# USB_Micro_Power_to_lab_board_2015-12-31.net
KiCad netlist of a schematic drawn in EAGLE
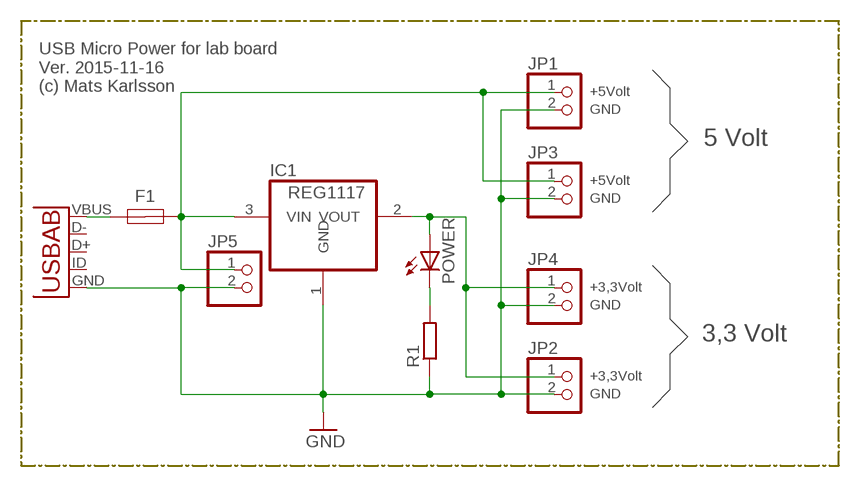
[diagram p0: schematic, sheet 1]

(export (version "E")
  (design (tool "Eeschema 10.0.6"))
  (components
    (comp (ref "F1")
      (value "LITTELFUSE_1812_500MA")
      (footprint "eagle-import:R1812")
      (fields (field (name "MPN") "1812L050PR"))
      (libsource (lib "eagle-import") (part "LITTELFUSE_1812_500MA"))
    )
    (comp (ref "IC1")
      (value "REG1117")
      (footprint "eagle-import:SOT223")
      (libsource (lib "eagle-import") (part "REG1117"))
    )
    (comp (ref "JP1")
      (value "PINHD-1X2")
      (footprint "eagle-import:1X02")
      (libsource (lib "eagle-import") (part "PINHD-1X2"))
    )
    (comp (ref "JP2")
      (value "PINHD-1X2")
      (footprint "eagle-import:1X02")
      (libsource (lib "eagle-import") (part "PINHD-1X2"))
    )
    (comp (ref "JP3")
      (value "PINHD-1X2")
      (footprint "eagle-import:1X02")
      (libsource (lib "eagle-import") (part "PINHD-1X2"))
    )
    (comp (ref "JP4")
      (value "PINHD-1X2")
      (footprint "eagle-import:1X02")
      (libsource (lib "eagle-import") (part "PINHD-1X2"))
    )
    (comp (ref "JP5")
      (value "PINHD-1X2")
      (footprint "eagle-import:1X02")
      (libsource (lib "eagle-import") (part "PINHD-1X2"))
    )
    (comp (ref "POWER")
      (value "LED3MM")
      (footprint "eagle-import:LED3MM")
      (libsource (lib "eagle-import") (part "LED3MM"))
    )
    (comp (ref "R1")
      (value "R-EU_0204/5")
      (footprint "eagle-import:0204_5")
      (libsource (lib "eagle-import") (part "R-EU_0204/5"))
    )
    (comp (ref "U1")
      (value "USB-ABUSB-AB-MICRO-SMD")
      (footprint "eagle-import:USB-AB-MICRO-SMD_VO2")
      (libsource (lib "eagle-import") (part "USB-ABUSB-AB-MICRO-SMD"))
    )
  )
  (nets
    (net (code "1") (name "GND") (class "Default")
      (node (ref "IC1") (pin "1") (pinfunction "GND_1") (pintype "power_in"))
      (node (ref "JP1") (pin "2") (pinfunction "2_2") (pintype "passive"))
      (node (ref "JP2") (pin "2") (pinfunction "2_2") (pintype "passive"))
      (node (ref "JP3") (pin "2") (pinfunction "2_2") (pintype "passive"))
      (node (ref "JP4") (pin "2") (pinfunction "2_2") (pintype "passive"))
      (node (ref "JP5") (pin "2") (pinfunction "2_2") (pintype "passive"))
      (node (ref "R1") (pin "1") (pinfunction "1_1") (pintype "passive"))
      (node (ref "U1") (pin "GND") (pinfunction "GND_GND") (pintype "bidirectional"))
    )
    (net (code "2") (name "Net-(F1-P$1)") (class "Default")
      (node (ref "F1") (pin "1") (pinfunction "P$1_1") (pintype "bidirectional"))
      (node (ref "U1") (pin "VBUS") (pinfunction "VBUS_VBUS") (pintype "bidirectional"))
    )
    (net (code "3") (name "Net-(F1-P$2)") (class "Default")
      (node (ref "F1") (pin "2") (pinfunction "P$2_2") (pintype "bidirectional"))
      (node (ref "IC1") (pin "3") (pinfunction "VIN_3") (pintype "input"))
      (node (ref "JP1") (pin "1") (pinfunction "1_1") (pintype "passive"))
      (node (ref "JP3") (pin "1") (pinfunction "1_1") (pintype "passive"))
      (node (ref "JP5") (pin "1") (pinfunction "1_1") (pintype "passive"))
    )
    (net (code "4") (name "Net-(IC1-VOUT)") (class "Default")
      (node (ref "IC1") (pin "2") (pinfunction "VOUT_2") (pintype "output"))
      (node (ref "JP2") (pin "1") (pinfunction "1_1") (pintype "passive"))
      (node (ref "JP4") (pin "1") (pinfunction "1_1") (pintype "passive"))
      (node (ref "POWER") (pin "A") (pinfunction "A_A") (pintype "passive"))
    )
    (net (code "5") (name "Net-(POWER-C)") (class "Default")
      (node (ref "POWER") (pin "K") (pinfunction "C_K") (pintype "passive"))
      (node (ref "R1") (pin "2") (pinfunction "2_2") (pintype "passive"))
    )
    (net (code "6") (name "unconnected-(U1-PadD+)") (class "Default")
      (node (ref "U1") (pin "D+") (pinfunction "D+_D+") (pintype "bidirectional"))
    )
    (net (code "7") (name "unconnected-(U1-PadD-)") (class "Default")
      (node (ref "U1") (pin "D-") (pinfunction "D-_D-") (pintype "bidirectional"))
    )
    (net (code "8") (name "unconnected-(U1-USBID-PadID)") (class "Default")
      (node (ref "U1") (pin "ID") (pinfunction "USBID_ID") (pintype "bidirectional"))
    )
  )
)
